# trophy-v2_2-second.net
KiCad netlist of a schematic drawn in EAGLE
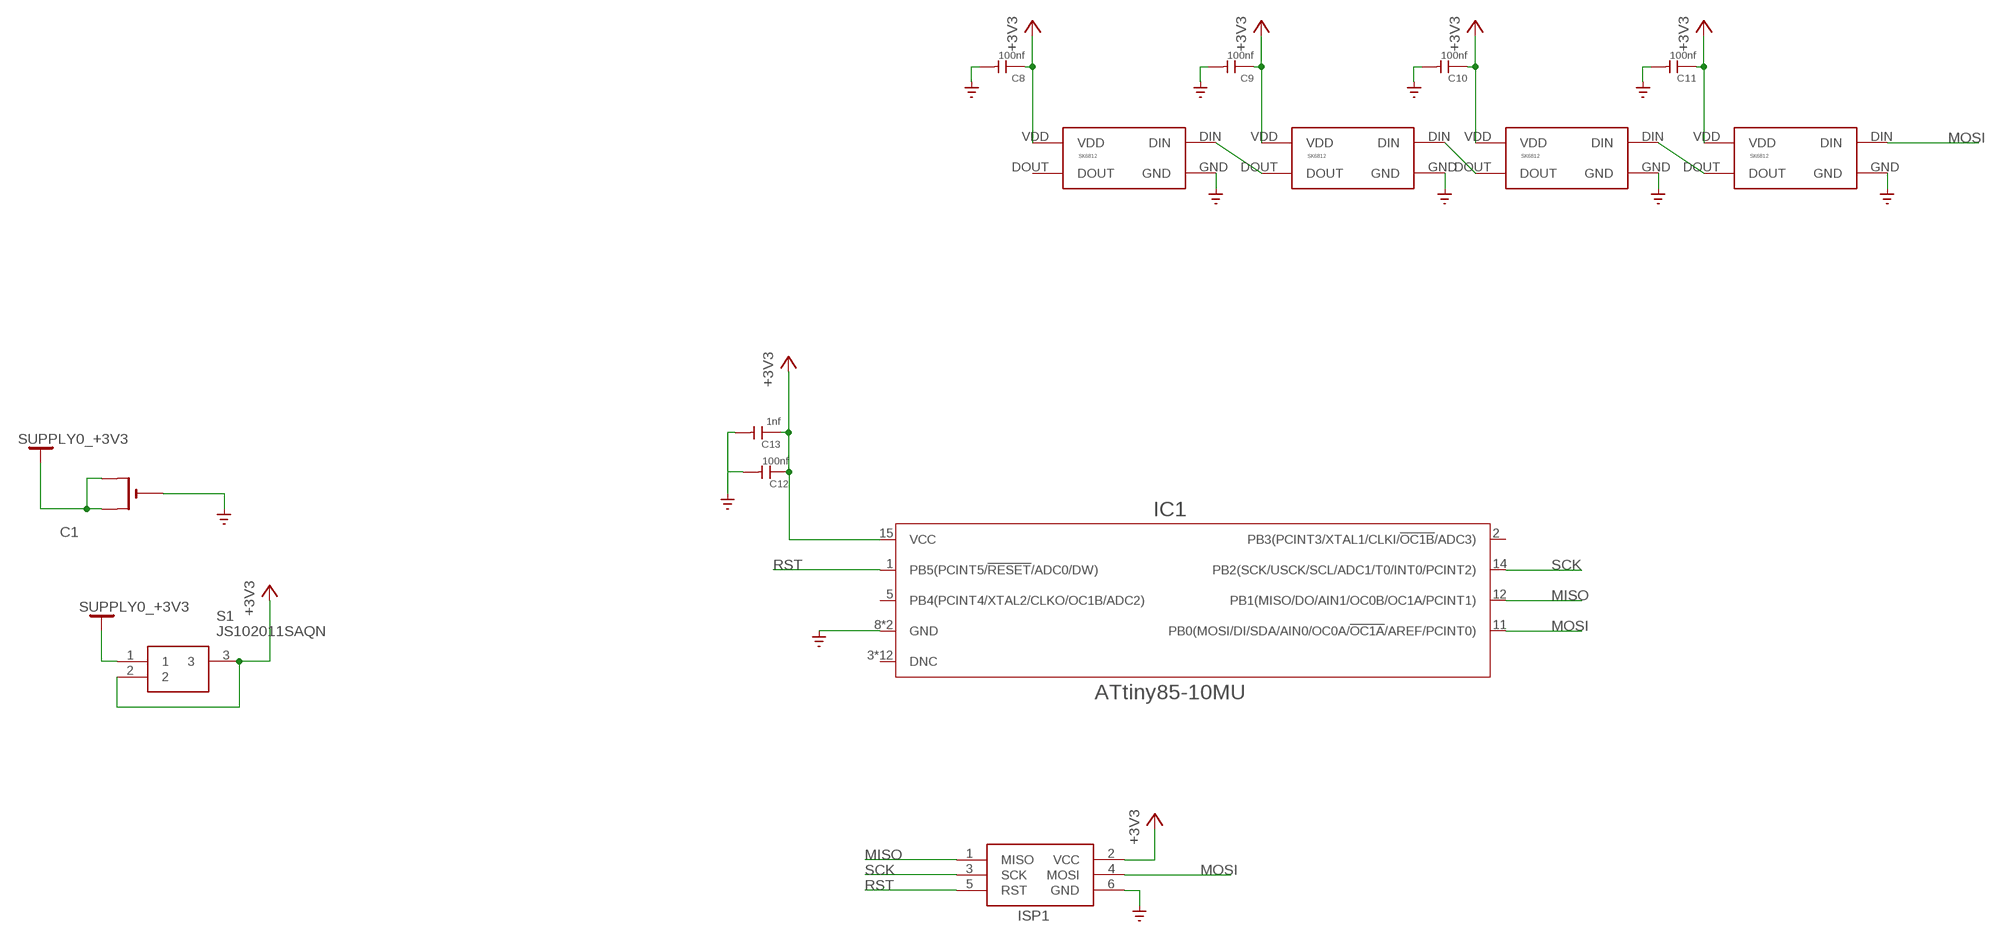
[diagram p0: schematic, sheet 1]

(export (version "E")
  (design (tool "Eeschema 10.0.6"))
  (components
    (comp (ref "C1")
      (value "CL2020")
      (footprint "eagle-import:CR2032-SMD")
      (libsource (lib "eagle-import") (part "CR2032SMT"))
    )
    (comp (ref "C8")
      (value "100nf")
      (footprint "eagle-import:C0603")
      (fields (field (name "MPN") "CC0603KRX7R9BB104"))
      (libsource (lib "eagle-import") (part "CERAMIC-100NF-50V-10%-X7R(0603)"))
    )
    (comp (ref "C9")
      (value "100nf")
      (footprint "eagle-import:C0603")
      (fields (field (name "MPN") "CC0603KRX7R9BB104"))
      (libsource (lib "eagle-import") (part "CERAMIC-100NF-50V-10%-X7R(0603)"))
    )
    (comp (ref "C10")
      (value "100nf")
      (footprint "eagle-import:C0603")
      (fields (field (name "MPN") "CC0603KRX7R9BB104"))
      (libsource (lib "eagle-import") (part "CERAMIC-100NF-50V-10%-X7R(0603)"))
    )
    (comp (ref "C11")
      (value "100nf")
      (footprint "eagle-import:C0603")
      (fields (field (name "MPN") "CC0603KRX7R9BB104"))
      (libsource (lib "eagle-import") (part "CERAMIC-100NF-50V-10%-X7R(0603)"))
    )
    (comp (ref "C12")
      (value "100nf")
      (footprint "eagle-import:C0603")
      (fields (field (name "MPN") "CC0603KRX7R9BB104"))
      (libsource (lib "eagle-import") (part "CERAMIC-100NF-50V-10%-X7R(0603)"))
    )
    (comp (ref "C13")
      (value "1nf")
      (footprint "eagle-import:C0603")
      (fields (field (name "MPN") "GRM1885C1H102JA01D"))
      (libsource (lib "eagle-import") (part "CERAMIC-1NF-50V-5%-C0G(0603)"))
    )
    (comp (ref "IC1")
      (value "ATtiny85-10MU")
      (footprint "eagle-import:QFN50P400X400X80-21T275")
      (fields (field (name "MANUFACTURER") "Microchip Technology"))
      (libsource (lib "eagle-import") (part "ATTINY-85_20PIN85-10MU"))
    )
    (comp (ref "ISP1")
      (value "AVRISP-6")
      (footprint "eagle-import:AVRISP")
      (libsource (lib "eagle-import") (part "AVRISP-6"))
    )
    (comp (ref "S1")
      (value "JS102011SAQN")
      (footprint "eagle-import:JS102011SAQN")
      (fields (field (name "MOUSER2_PART_NUMBER") "611-JS102011SAQN"))
      (libsource (lib "eagle-import") (part "JS102011SAQN"))
    )
    (comp (ref "U$1")
      (value "SK6812")
      (footprint "eagle-import:5050")
      (libsource (lib "eagle-import") (part "SK6812"))
    )
    (comp (ref "U$2")
      (value "SK6812")
      (footprint "eagle-import:5050")
      (libsource (lib "eagle-import") (part "SK6812"))
    )
    (comp (ref "U$3")
      (value "SK6812")
      (footprint "eagle-import:5050")
      (libsource (lib "eagle-import") (part "SK6812"))
    )
    (comp (ref "U$4")
      (value "SK6812")
      (footprint "eagle-import:5050")
      (libsource (lib "eagle-import") (part "SK6812"))
    )
  )
  (nets
    (net (code "1") (name "+3V3") (class "Default")
      (node (ref "C10") (pin "1") (pinfunction "1_1") (pintype "passive"))
      (node (ref "C11") (pin "1") (pinfunction "1_1") (pintype "passive"))
      (node (ref "C12") (pin "1") (pinfunction "1_1") (pintype "passive"))
      (node (ref "C13") (pin "1") (pinfunction "1_1") (pintype "passive"))
      (node (ref "C8") (pin "1") (pinfunction "1_1") (pintype "passive"))
      (node (ref "C9") (pin "1") (pinfunction "1_1") (pintype "passive"))
      (node (ref "IC1") (pin "15") (pinfunction "VCC_15") (pintype "power_in"))
      (node (ref "ISP1") (pin "2") (pinfunction "VCC_2") (pintype "power_in"))
      (node (ref "S1") (pin "2") (pinfunction "2_2") (pintype "bidirectional"))
      (node (ref "S1") (pin "3") (pinfunction "3_3") (pintype "bidirectional"))
      (node (ref "U$1") (pin "VDD") (pinfunction "VDD_VDD") (pintype "bidirectional"))
      (node (ref "U$2") (pin "VDD") (pinfunction "VDD_VDD") (pintype "bidirectional"))
      (node (ref "U$3") (pin "VDD") (pinfunction "VDD_VDD") (pintype "bidirectional"))
      (node (ref "U$4") (pin "VDD") (pinfunction "VDD_VDD") (pintype "bidirectional"))
    )
    (net (code "2") (name "/MISO") (class "Default")
      (node (ref "IC1") (pin "12") (pinfunction "PB1(MISO/DO/AIN1/OC0B/OC1A/PCINT1)_12") (pintype "bidirectional"))
      (node (ref "ISP1") (pin "1") (pinfunction "MISO_1") (pintype "input"))
    )
    (net (code "3") (name "/MOSI") (class "Default")
      (node (ref "IC1") (pin "11") (pinfunction "PB0(MOSI/DI/SDA/AIN0/OC0A/~{OC1A}/AREF/PCINT0)_11") (pintype "bidirectional"))
      (node (ref "ISP1") (pin "4") (pinfunction "MOSI_4") (pintype "output"))
      (node (ref "U$1") (pin "DIN") (pinfunction "DIN_DIN") (pintype "bidirectional"))
    )
    (net (code "4") (name "/RST") (class "Default")
      (node (ref "IC1") (pin "1") (pinfunction "PB5(PCINT5/~{RESET}/ADC0/DW)_1") (pintype "bidirectional"))
      (node (ref "ISP1") (pin "5") (pinfunction "RST_5") (pintype "output"))
    )
    (net (code "5") (name "/SCK") (class "Default")
      (node (ref "IC1") (pin "14") (pinfunction "PB2(SCK/USCK/SCL/ADC1/T0/INT0/PCINT2)_14") (pintype "bidirectional"))
      (node (ref "ISP1") (pin "3") (pinfunction "SCK_3") (pintype "output"))
    )
    (net (code "6") (name "Net-(U$1-PadDOUT)") (class "Default")
      (node (ref "U$1") (pin "DOUT") (pinfunction "DOUT_DOUT") (pintype "bidirectional"))
      (node (ref "U$2") (pin "DIN") (pinfunction "DIN_DIN") (pintype "bidirectional"))
    )
    (net (code "7") (name "Net-(U$2-PadDOUT)") (class "Default")
      (node (ref "U$2") (pin "DOUT") (pinfunction "DOUT_DOUT") (pintype "bidirectional"))
      (node (ref "U$3") (pin "DIN") (pinfunction "DIN_DIN") (pintype "bidirectional"))
    )
    (net (code "8") (name "Net-(U$3-PadDOUT)") (class "Default")
      (node (ref "U$3") (pin "DOUT") (pinfunction "DOUT_DOUT") (pintype "bidirectional"))
      (node (ref "U$4") (pin "DIN") (pinfunction "DIN_DIN") (pintype "bidirectional"))
    )
    (net (code "9") (name "SUPPLY0_+3V3") (class "Default")
      (node (ref "C1") (pin "+$1") (pinfunction "+_+$1") (pintype "passive"))
      (node (ref "C1") (pin "+$2") (pinfunction "+1_+$2") (pintype "passive"))
      (node (ref "S1") (pin "1") (pinfunction "1_1") (pintype "bidirectional"))
    )
    (net (code "10") (name "SUPPLY0_GND_") (class "Default")
      (node (ref "C1") (pin "-") (pinfunction "-_-") (pintype "passive"))
      (node (ref "C10") (pin "2") (pinfunction "2_2") (pintype "passive"))
      (node (ref "C11") (pin "2") (pinfunction "2_2") (pintype "passive"))
      (node (ref "C12") (pin "2") (pinfunction "2_2") (pintype "passive"))
      (node (ref "C13") (pin "2") (pinfunction "2_2") (pintype "passive"))
      (node (ref "C8") (pin "2") (pinfunction "2_2") (pintype "passive"))
      (node (ref "C9") (pin "2") (pinfunction "2_2") (pintype "passive"))
      (node (ref "IC1") (pin "21") (pinfunction "GND_21") (pintype "power_in"))
      (node (ref "IC1") (pin "8") (pinfunction "GND_8") (pintype "power_in"))
      (node (ref "ISP1") (pin "6") (pinfunction "GND_6") (pintype "power_in"))
      (node (ref "U$1") (pin "GND") (pinfunction "GND_GND") (pintype "bidirectional"))
      (node (ref "U$2") (pin "GND") (pinfunction "GND_GND") (pintype "bidirectional"))
      (node (ref "U$3") (pin "GND") (pinfunction "GND_GND") (pintype "bidirectional"))
      (node (ref "U$4") (pin "GND") (pinfunction "GND_GND") (pintype "bidirectional"))
    )
    (net (code "11") (name "unconnected-(IC1-DNC-Pad3)") (class "Default")
      (node (ref "IC1") (pin "3") (pinfunction "DNC_3") (pintype "no_connect"))
    )
    (net (code "12") (name "unconnected-(IC1-DNC-Pad4)") (class "Default")
      (node (ref "IC1") (pin "4") (pinfunction "DNC_4") (pintype "no_connect"))
    )
    (net (code "13") (name "unconnected-(IC1-DNC-Pad6)") (class "Default")
      (node (ref "IC1") (pin "6") (pinfunction "DNC_6") (pintype "no_connect"))
    )
    (net (code "14") (name "unconnected-(IC1-DNC-Pad7)") (class "Default")
      (node (ref "IC1") (pin "7") (pinfunction "DNC_7") (pintype "no_connect"))
    )
    (net (code "15") (name "unconnected-(IC1-DNC-Pad9)") (class "Default")
      (node (ref "IC1") (pin "9") (pinfunction "DNC_9") (pintype "no_connect"))
    )
    (net (code "16") (name "unconnected-(IC1-DNC-Pad10)") (class "Default")
      (node (ref "IC1") (pin "10") (pinfunction "DNC_10") (pintype "no_connect"))
    )
    (net (code "17") (name "unconnected-(IC1-DNC-Pad13)") (class "Default")
      (node (ref "IC1") (pin "13") (pinfunction "DNC_13") (pintype "no_connect"))
    )
    (net (code "18") (name "unconnected-(IC1-DNC-Pad16)") (class "Default")
      (node (ref "IC1") (pin "16") (pinfunction "DNC_16") (pintype "no_connect"))
    )
    (net (code "19") (name "unconnected-(IC1-DNC-Pad17)") (class "Default")
      (node (ref "IC1") (pin "17") (pinfunction "DNC_17") (pintype "no_connect"))
    )
    (net (code "20") (name "unconnected-(IC1-DNC-Pad18)") (class "Default")
      (node (ref "IC1") (pin "18") (pinfunction "DNC_18") (pintype "no_connect"))
    )
    (net (code "21") (name "unconnected-(IC1-DNC-Pad19)") (class "Default")
      (node (ref "IC1") (pin "19") (pinfunction "DNC_19") (pintype "no_connect"))
    )
    (net (code "22") (name "unconnected-(IC1-DNC-Pad20)") (class "Default")
      (node (ref "IC1") (pin "20") (pinfunction "DNC_20") (pintype "no_connect"))
    )
    (net (code "23") (name "unconnected-(IC1-PB3(PCINT3{slash}XTAL1{slash}CLKI{slash}~{OC1B}{slash}ADC3)-Pad2)") (class "Default")
      (node (ref "IC1") (pin "2") (pinfunction "PB3(PCINT3/XTAL1/CLKI/~{OC1B}/ADC3)_2") (pintype "bidirectional"))
    )
    (net (code "24") (name "unconnected-(IC1-PB4(PCINT4{slash}XTAL2{slash}CLKO{slash}OC1B{slash}ADC2)-Pad5)") (class "Default")
      (node (ref "IC1") (pin "5") (pinfunction "PB4(PCINT4/XTAL2/CLKO/OC1B/ADC2)_5") (pintype "bidirectional"))
    )
    (net (code "25") (name "unconnected-(U$4-PadDOUT)") (class "Default")
      (node (ref "U$4") (pin "DOUT") (pinfunction "DOUT_DOUT") (pintype "bidirectional"))
    )
  )
)
